# RTU.net
KiCad netlist of a schematic drawn in EAGLE
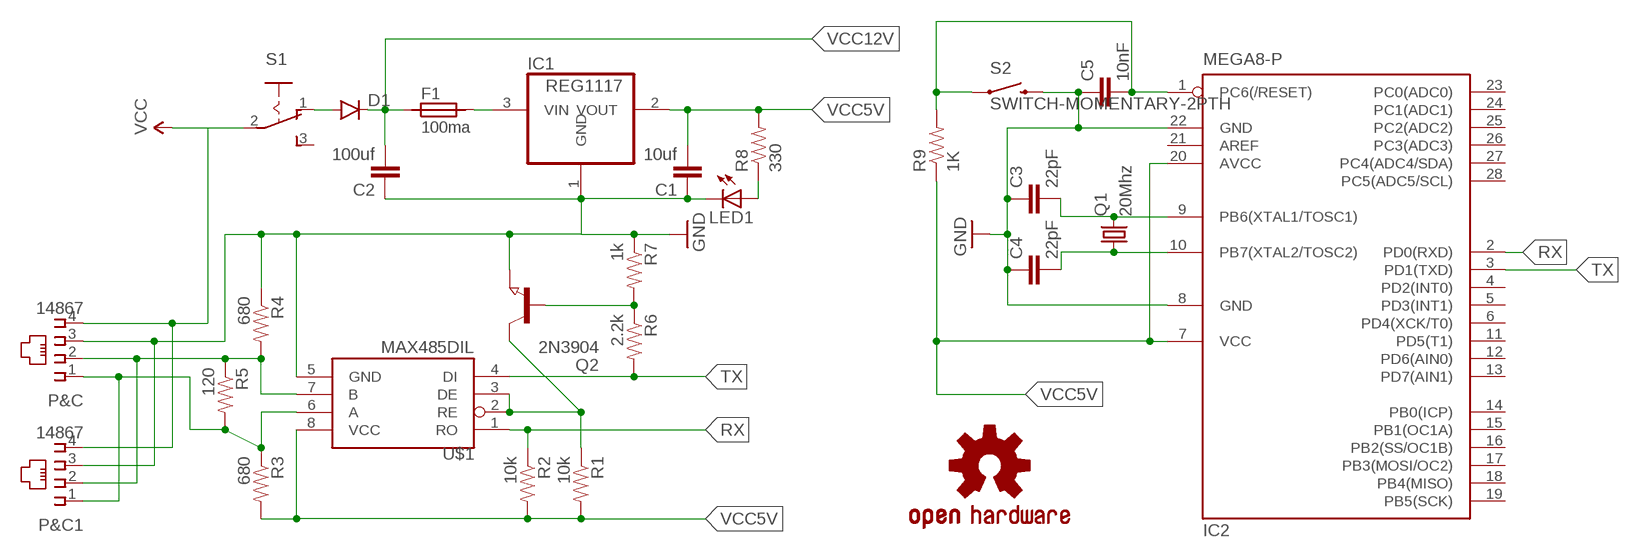
[diagram p0: schematic, sheet 1]

(export (version "E")
  (design (tool "Eeschema 10.0.6"))
  (components
    (comp (ref "C1")
      (value "10uf")
      (footprint "eagle-import:0805")
      (libsource (lib "eagle-import") (part "CAP0805"))
    )
    (comp (ref "C2")
      (value "100uf")
      (footprint "eagle-import:0805")
      (libsource (lib "eagle-import") (part "CAP0805"))
    )
    (comp (ref "C3")
      (value "22pF")
      (footprint "eagle-import:0805")
      (libsource (lib "eagle-import") (part "CAP0805"))
    )
    (comp (ref "C4")
      (value "22pF")
      (footprint "eagle-import:0805")
      (libsource (lib "eagle-import") (part "CAP0805"))
    )
    (comp (ref "C5")
      (value "10nF")
      (footprint "eagle-import:0805")
      (libsource (lib "eagle-import") (part "CAP0805"))
    )
    (comp (ref "D1")
      (value "DIODESMA")
      (footprint "eagle-import:SMA-DIODE")
      (libsource (lib "eagle-import") (part "DIODESMA"))
    )
    (comp (ref "F1")
      (value "100ma")
      (footprint "eagle-import:1820")
      (libsource (lib "eagle-import") (part "SIBA194600"))
    )
    (comp (ref "IC1")
      (value "REG1117")
      (footprint "eagle-import:SOT223")
      (libsource (lib "eagle-import") (part "REG1117"))
    )
    (comp (ref "IC2")
      (value "MEGA8-P")
      (footprint "eagle-import:DIL28-3")
      (libsource (lib "eagle-import") (part "MEGA8-P"))
    )
    (comp (ref "LED1")
      (value "LEDCHIP-LED0805")
      (footprint "eagle-import:CHIP-LED0805")
      (libsource (lib "eagle-import") (part "LEDCHIP-LED0805"))
    )
    (comp (ref "LOGO1")
      (value "OSHW-LOGOL")
      (footprint "eagle-import:OSHW-LOGO-L")
      (libsource (lib "eagle-import") (part "OSHW-LOGOL"))
    )
    (comp (ref "P&C")
      (value "14867")
      (footprint "eagle-import:14867")
      (libsource (lib "eagle-import") (part "14867"))
    )
    (comp (ref "P&C1")
      (value "14867")
      (footprint "eagle-import:14867")
      (libsource (lib "eagle-import") (part "14867"))
    )
    (comp (ref "Q1")
      (value "20Mhz")
      (footprint "eagle-import:SM49")
      (libsource (lib "eagle-import") (part "CRYSTALSM49"))
    )
    (comp (ref "Q2")
      (value "2N3904")
      (footprint "eagle-import:SOT23")
      (libsource (lib "eagle-import") (part "NPN-TRANSISTOR_SOT23"))
    )
    (comp (ref "R1")
      (value "10k")
      (footprint "eagle-import:0805")
      (libsource (lib "eagle-import") (part "RESISTOR0805-RES"))
    )
    (comp (ref "R2")
      (value "10k")
      (footprint "eagle-import:0805")
      (libsource (lib "eagle-import") (part "RESISTOR0805-RES"))
    )
    (comp (ref "R3")
      (value "680")
      (footprint "eagle-import:0805")
      (libsource (lib "eagle-import") (part "RESISTOR0805-RES"))
    )
    (comp (ref "R4")
      (value "680")
      (footprint "eagle-import:0805")
      (libsource (lib "eagle-import") (part "RESISTOR0805-RES"))
    )
    (comp (ref "R5")
      (value "120")
      (footprint "eagle-import:0805")
      (libsource (lib "eagle-import") (part "RESISTOR0805-RES"))
    )
    (comp (ref "R6")
      (value "2.2k")
      (footprint "eagle-import:0805")
      (libsource (lib "eagle-import") (part "RESISTOR0805-RES"))
    )
    (comp (ref "R7")
      (value "1k")
      (footprint "eagle-import:0805")
      (libsource (lib "eagle-import") (part "RESISTOR0805-RES"))
    )
    (comp (ref "R8")
      (value "330")
      (footprint "eagle-import:0805")
      (libsource (lib "eagle-import") (part "RESISTOR0805-RES"))
    )
    (comp (ref "R9")
      (value "1K")
      (footprint "eagle-import:0805")
      (libsource (lib "eagle-import") (part "RESISTOR0805-RES"))
    )
    (comp (ref "S1")
      (value "255SB")
      (footprint "eagle-import:255SB")
      (libsource (lib "eagle-import") (part "255SB"))
    )
    (comp (ref "S2")
      (value "SWITCH-MOMENTARY-2PTH")
      (footprint "eagle-import:TACTILE-PTH")
      (libsource (lib "eagle-import") (part "SWITCH-MOMENTARY-2PTH"))
    )
    (comp (ref "U$1")
      (value "MAX485DIL")
      (footprint "eagle-import:DIL08")
      (libsource (lib "eagle-import") (part "MAX485DIL"))
    )
  )
  (nets
    (net (code "1") (name "GND") (class "Default")
      (node (ref "C1") (pin "1") (pinfunction "1_1") (pintype "passive"))
      (node (ref "C2") (pin "1") (pinfunction "1_1") (pintype "passive"))
      (node (ref "C3") (pin "1") (pinfunction "1_1") (pintype "passive"))
      (node (ref "C4") (pin "1") (pinfunction "1_1") (pintype "passive"))
      (node (ref "C5") (pin "1") (pinfunction "1_1") (pintype "passive"))
      (node (ref "IC1") (pin "1") (pinfunction "GND_1") (pintype "power_in"))
      (node (ref "IC2") (pin "22") (pinfunction "GND_22") (pintype "power_in"))
      (node (ref "IC2") (pin "8") (pinfunction "GND_8") (pintype "power_in"))
      (node (ref "LED1") (pin "C") (pinfunction "C_C") (pintype "passive"))
      (node (ref "P&C") (pin "3") (pinfunction "3_3") (pintype "passive"))
      (node (ref "P&C1") (pin "3") (pinfunction "3_3") (pintype "passive"))
      (node (ref "Q2") (pin "2") (pinfunction "E_2") (pintype "passive"))
      (node (ref "R4") (pin "1") (pinfunction "1_1") (pintype "passive"))
      (node (ref "R7") (pin "1") (pinfunction "1_1") (pintype "passive"))
      (node (ref "S2") (pin "3") (pinfunction "2_3") (pintype "passive"))
      (node (ref "U$1") (pin "5") (pinfunction "GND_5") (pintype "bidirectional"))
    )
    (net (code "2") (name "Net-(IC1-VIN)") (class "Default")
      (node (ref "F1") (pin "2") (pinfunction "2_2") (pintype "passive"))
      (node (ref "IC1") (pin "3") (pinfunction "VIN_3") (pintype "input"))
    )
    (net (code "3") (name "Net-(IC2-PB6(XTAL1{slash}TOSC1))") (class "Default")
      (node (ref "C3") (pin "2") (pinfunction "2_2") (pintype "passive"))
      (node (ref "IC2") (pin "9") (pinfunction "PB6(XTAL1/TOSC1)_9") (pintype "bidirectional"))
      (node (ref "Q1") (pin "2") (pinfunction "2_2") (pintype "passive"))
    )
    (net (code "4") (name "Net-(IC2-PB7(XTAL2{slash}TOSC2))") (class "Default")
      (node (ref "C4") (pin "2") (pinfunction "2_2") (pintype "passive"))
      (node (ref "IC2") (pin "10") (pinfunction "PB7(XTAL2/TOSC2)_10") (pintype "bidirectional"))
      (node (ref "Q1") (pin "1") (pinfunction "1_1") (pintype "passive"))
    )
    (net (code "5") (name "Net-(IC2-PC6({slash}RESET))") (class "Default")
      (node (ref "C5") (pin "2") (pinfunction "2_2") (pintype "passive"))
      (node (ref "IC2") (pin "1") (pinfunction "PC6(/RESET)_1") (pintype "bidirectional"))
      (node (ref "R9") (pin "2") (pinfunction "2_2") (pintype "passive"))
      (node (ref "S2") (pin "1") (pinfunction "1_1") (pintype "passive"))
    )
    (net (code "6") (name "Net-(LED1-PadA)") (class "Default")
      (node (ref "LED1") (pin "A") (pinfunction "A_A") (pintype "passive"))
      (node (ref "R8") (pin "1") (pinfunction "1_1") (pintype "passive"))
    )
    (net (code "7") (name "Net-(Q2-B)") (class "Default")
      (node (ref "Q2") (pin "1") (pinfunction "B_1") (pintype "passive"))
      (node (ref "R6") (pin "1") (pinfunction "1_1") (pintype "passive"))
      (node (ref "R7") (pin "2") (pinfunction "2_2") (pintype "passive"))
    )
    (net (code "8") (name "Net-(Q2-C)") (class "Default")
      (node (ref "Q2") (pin "3") (pinfunction "C_3") (pintype "passive"))
      (node (ref "R1") (pin "1") (pinfunction "1_1") (pintype "passive"))
      (node (ref "U$1") (pin "2") (pinfunction "RE_2") (pintype "bidirectional"))
      (node (ref "U$1") (pin "3") (pinfunction "DE_3") (pintype "bidirectional"))
    )
    (net (code "9") (name "Net-(S1-O)") (class "Default")
      (node (ref "D1") (pin "A") (pinfunction "A_A") (pintype "passive"))
      (node (ref "S1") (pin "1") (pinfunction "O_1") (pintype "passive"))
    )
    (net (code "10") (name "Net-(U$1-A)") (class "Default")
      (node (ref "P&C") (pin "1") (pinfunction "1_1") (pintype "passive"))
      (node (ref "P&C1") (pin "1") (pinfunction "1_1") (pintype "passive"))
      (node (ref "R3") (pin "1") (pinfunction "1_1") (pintype "passive"))
      (node (ref "R5") (pin "2") (pinfunction "2_2") (pintype "passive"))
      (node (ref "U$1") (pin "6") (pinfunction "A_6") (pintype "bidirectional"))
    )
    (net (code "11") (name "Net-(U$1-B)") (class "Default")
      (node (ref "P&C") (pin "2") (pinfunction "2_2") (pintype "passive"))
      (node (ref "P&C1") (pin "2") (pinfunction "2_2") (pintype "passive"))
      (node (ref "R4") (pin "2") (pinfunction "2_2") (pintype "passive"))
      (node (ref "R5") (pin "1") (pinfunction "1_1") (pintype "passive"))
      (node (ref "U$1") (pin "7") (pinfunction "B_7") (pintype "bidirectional"))
    )
    (net (code "12") (name "RX") (class "Default")
      (node (ref "IC2") (pin "2") (pinfunction "PD0(RXD)_2") (pintype "bidirectional"))
      (node (ref "R2") (pin "1") (pinfunction "1_1") (pintype "passive"))
      (node (ref "U$1") (pin "1") (pinfunction "RO_1") (pintype "bidirectional"))
    )
    (net (code "13") (name "TX") (class "Default")
      (node (ref "IC2") (pin "3") (pinfunction "PD1(TXD)_3") (pintype "bidirectional"))
      (node (ref "R6") (pin "2") (pinfunction "2_2") (pintype "passive"))
      (node (ref "U$1") (pin "4") (pinfunction "DI_4") (pintype "bidirectional"))
    )
    (net (code "14") (name "VCC") (class "Default")
      (node (ref "P&C") (pin "4") (pinfunction "4_4") (pintype "passive"))
      (node (ref "P&C1") (pin "4") (pinfunction "4_4") (pintype "passive"))
      (node (ref "S1") (pin "2") (pinfunction "P_2") (pintype "passive"))
    )
    (net (code "15") (name "VCC5V") (class "Default")
      (node (ref "C1") (pin "2") (pinfunction "2_2") (pintype "passive"))
      (node (ref "IC1") (pin "2") (pinfunction "VOUT_2") (pintype "output"))
      (node (ref "IC2") (pin "20") (pinfunction "AVCC_20") (pintype "power_in"))
      (node (ref "IC2") (pin "7") (pinfunction "VCC_7") (pintype "power_in"))
      (node (ref "R1") (pin "2") (pinfunction "2_2") (pintype "passive"))
      (node (ref "R2") (pin "2") (pinfunction "2_2") (pintype "passive"))
      (node (ref "R3") (pin "2") (pinfunction "2_2") (pintype "passive"))
      (node (ref "R8") (pin "2") (pinfunction "2_2") (pintype "passive"))
      (node (ref "R9") (pin "1") (pinfunction "1_1") (pintype "passive"))
      (node (ref "U$1") (pin "8") (pinfunction "VCC_8") (pintype "bidirectional"))
    )
    (net (code "16") (name "VCC12V") (class "Default")
      (node (ref "C2") (pin "2") (pinfunction "2_2") (pintype "passive"))
      (node (ref "D1") (pin "C") (pinfunction "C_C") (pintype "passive"))
      (node (ref "F1") (pin "1") (pinfunction "1_1") (pintype "passive"))
    )
    (net (code "17") (name "unconnected-(IC2-AREF-Pad21)") (class "Default")
      (node (ref "IC2") (pin "21") (pinfunction "AREF_21") (pintype "passive"))
    )
    (net (code "18") (name "unconnected-(IC2-PB0(ICP)-Pad14)") (class "Default")
      (node (ref "IC2") (pin "14") (pinfunction "PB0(ICP)_14") (pintype "bidirectional"))
    )
    (net (code "19") (name "unconnected-(IC2-PB1(OC1A)-Pad15)") (class "Default")
      (node (ref "IC2") (pin "15") (pinfunction "PB1(OC1A)_15") (pintype "bidirectional"))
    )
    (net (code "20") (name "unconnected-(IC2-PB2(SS{slash}OC1B)-Pad16)") (class "Default")
      (node (ref "IC2") (pin "16") (pinfunction "PB2(SS/OC1B)_16") (pintype "bidirectional"))
    )
    (net (code "21") (name "unconnected-(IC2-PB3(MOSI{slash}OC2)-Pad17)") (class "Default")
      (node (ref "IC2") (pin "17") (pinfunction "PB3(MOSI/OC2)_17") (pintype "bidirectional"))
    )
    (net (code "22") (name "unconnected-(IC2-PB4(MISO)-Pad18)") (class "Default")
      (node (ref "IC2") (pin "18") (pinfunction "PB4(MISO)_18") (pintype "bidirectional"))
    )
    (net (code "23") (name "unconnected-(IC2-PB5(SCK)-Pad19)") (class "Default")
      (node (ref "IC2") (pin "19") (pinfunction "PB5(SCK)_19") (pintype "bidirectional"))
    )
    (net (code "24") (name "unconnected-(IC2-PC0(ADC0)-Pad23)") (class "Default")
      (node (ref "IC2") (pin "23") (pinfunction "PC0(ADC0)_23") (pintype "bidirectional"))
    )
    (net (code "25") (name "unconnected-(IC2-PC1(ADC1)-Pad24)") (class "Default")
      (node (ref "IC2") (pin "24") (pinfunction "PC1(ADC1)_24") (pintype "bidirectional"))
    )
    (net (code "26") (name "unconnected-(IC2-PC2(ADC2)-Pad25)") (class "Default")
      (node (ref "IC2") (pin "25") (pinfunction "PC2(ADC2)_25") (pintype "bidirectional"))
    )
    (net (code "27") (name "unconnected-(IC2-PC3(ADC3)-Pad26)") (class "Default")
      (node (ref "IC2") (pin "26") (pinfunction "PC3(ADC3)_26") (pintype "bidirectional"))
    )
    (net (code "28") (name "unconnected-(IC2-PC4(ADC4{slash}SDA)-Pad27)") (class "Default")
      (node (ref "IC2") (pin "27") (pinfunction "PC4(ADC4/SDA)_27") (pintype "bidirectional"))
    )
    (net (code "29") (name "unconnected-(IC2-PC5(ADC5{slash}SCL)-Pad28)") (class "Default")
      (node (ref "IC2") (pin "28") (pinfunction "PC5(ADC5/SCL)_28") (pintype "bidirectional"))
    )
    (net (code "30") (name "unconnected-(IC2-PD2(INT0)-Pad4)") (class "Default")
      (node (ref "IC2") (pin "4") (pinfunction "PD2(INT0)_4") (pintype "bidirectional"))
    )
    (net (code "31") (name "unconnected-(IC2-PD3(INT1)-Pad5)") (class "Default")
      (node (ref "IC2") (pin "5") (pinfunction "PD3(INT1)_5") (pintype "bidirectional"))
    )
    (net (code "32") (name "unconnected-(IC2-PD4(XCK{slash}T0)-Pad6)") (class "Default")
      (node (ref "IC2") (pin "6") (pinfunction "PD4(XCK/T0)_6") (pintype "bidirectional"))
    )
    (net (code "33") (name "unconnected-(IC2-PD5(T1)-Pad11)") (class "Default")
      (node (ref "IC2") (pin "11") (pinfunction "PD5(T1)_11") (pintype "bidirectional"))
    )
    (net (code "34") (name "unconnected-(IC2-PD6(AIN0)-Pad12)") (class "Default")
      (node (ref "IC2") (pin "12") (pinfunction "PD6(AIN0)_12") (pintype "bidirectional"))
    )
    (net (code "35") (name "unconnected-(IC2-PD7(AIN1)-Pad13)") (class "Default")
      (node (ref "IC2") (pin "13") (pinfunction "PD7(AIN1)_13") (pintype "bidirectional"))
    )
    (net (code "36") (name "unconnected-(S1-S-Pad3)") (class "Default")
      (node (ref "S1") (pin "3") (pinfunction "S_3") (pintype "passive"))
    )
  )
)
